# Tilty_Template.net
KiCad netlist of a schematic drawn in EAGLE
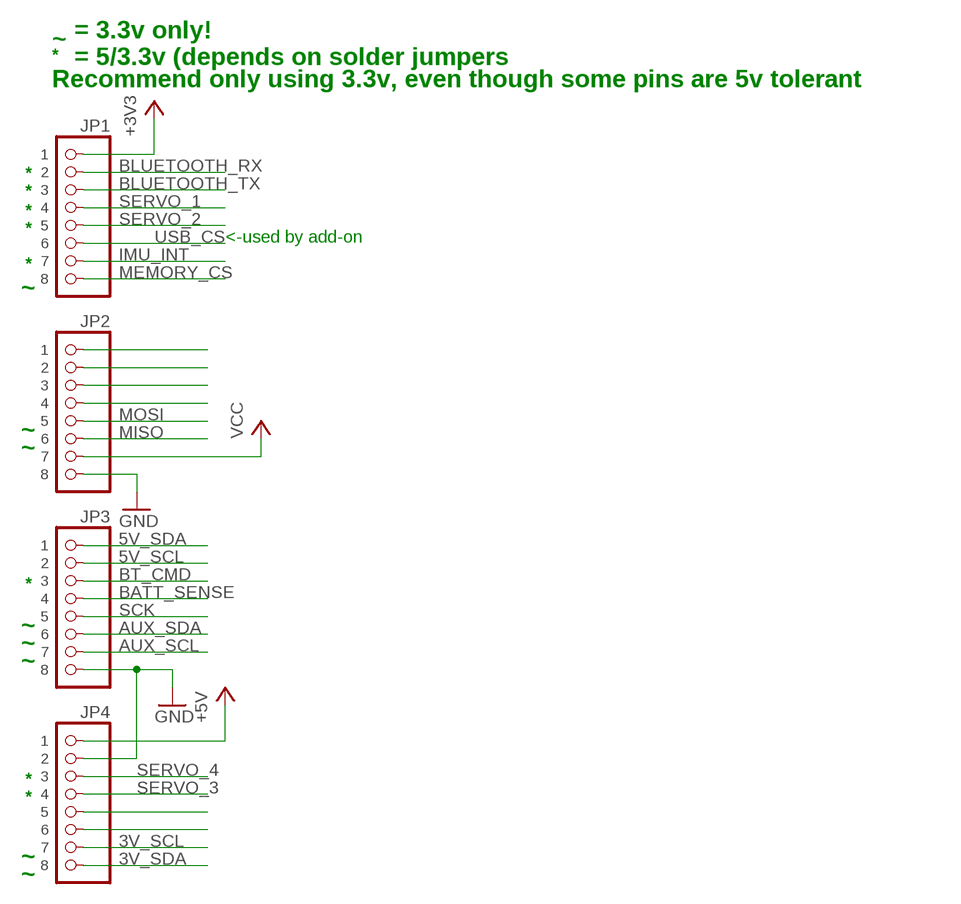
[diagram p0: schematic, sheet 1]

(export (version "E")
  (design (tool "Eeschema 10.0.6"))
  (components
    (comp (ref "JP1")
      (value "8-PIN_HEADER")
      (footprint "eagle-import:8-PIN_RECEPTACLE_LOCK_NO-SS")
      (libsource (lib "eagle-import") (part "8-PIN_HEADER"))
    )
    (comp (ref "JP2")
      (value "8-PIN_HEADER")
      (footprint "eagle-import:8-PIN_RECEPTACLE_LOCK_NO-SS")
      (libsource (lib "eagle-import") (part "8-PIN_HEADER"))
    )
    (comp (ref "JP3")
      (value "8-PIN_HEADER")
      (footprint "eagle-import:8-PIN_RECEPTACLE_LOCK_NO-SS")
      (libsource (lib "eagle-import") (part "8-PIN_HEADER"))
    )
    (comp (ref "JP4")
      (value "8-PIN_HEADER")
      (footprint "eagle-import:8-PIN_RECEPTACLE_LOCK_NO-SS")
      (libsource (lib "eagle-import") (part "8-PIN_HEADER"))
    )
  )
  (nets
    (net (code "1") (name "+3V3") (class "Default")
      (node (ref "JP1") (pin "P$1") (pinfunction "1_P$1") (pintype "passive"))
    )
    (net (code "2") (name "+5V") (class "Default")
      (node (ref "JP4") (pin "P$1") (pinfunction "1_P$1") (pintype "passive"))
    )
    (net (code "3") (name "/3V_SCL") (class "Default")
      (node (ref "JP4") (pin "P$7") (pinfunction "7_P$7") (pintype "passive"))
    )
    (net (code "4") (name "/3V_SDA") (class "Default")
      (node (ref "JP4") (pin "P$8") (pinfunction "8_P$8") (pintype "passive"))
    )
    (net (code "5") (name "/5V_SCL") (class "Default")
      (node (ref "JP3") (pin "P$2") (pinfunction "2_P$2") (pintype "passive"))
    )
    (net (code "6") (name "/5V_SDA") (class "Default")
      (node (ref "JP3") (pin "P$1") (pinfunction "1_P$1") (pintype "passive"))
    )
    (net (code "7") (name "/AUX_SCL") (class "Default")
      (node (ref "JP3") (pin "P$7") (pinfunction "7_P$7") (pintype "passive"))
    )
    (net (code "8") (name "/AUX_SDA") (class "Default")
      (node (ref "JP3") (pin "P$6") (pinfunction "6_P$6") (pintype "passive"))
    )
    (net (code "9") (name "/BATT_SENSE") (class "Default")
      (node (ref "JP3") (pin "P$4") (pinfunction "4_P$4") (pintype "passive"))
    )
    (net (code "10") (name "/BLUETOOTH_RX") (class "Default")
      (node (ref "JP1") (pin "P$2") (pinfunction "2_P$2") (pintype "passive"))
    )
    (net (code "11") (name "/BLUETOOTH_TX") (class "Default")
      (node (ref "JP1") (pin "P$3") (pinfunction "3_P$3") (pintype "passive"))
    )
    (net (code "12") (name "/BT_CMD") (class "Default")
      (node (ref "JP3") (pin "P$3") (pinfunction "3_P$3") (pintype "passive"))
    )
    (net (code "13") (name "/IMU_INT") (class "Default")
      (node (ref "JP1") (pin "P$7") (pinfunction "7_P$7") (pintype "passive"))
    )
    (net (code "14") (name "/MEMORY_CS") (class "Default")
      (node (ref "JP1") (pin "P$8") (pinfunction "8_P$8") (pintype "passive"))
    )
    (net (code "15") (name "/MISO") (class "Default")
      (node (ref "JP2") (pin "P$6") (pinfunction "6_P$6") (pintype "passive"))
    )
    (net (code "16") (name "/MOSI") (class "Default")
      (node (ref "JP2") (pin "P$5") (pinfunction "5_P$5") (pintype "passive"))
    )
    (net (code "17") (name "/SCK") (class "Default")
      (node (ref "JP3") (pin "P$5") (pinfunction "5_P$5") (pintype "passive"))
    )
    (net (code "18") (name "/SERVO_1") (class "Default")
      (node (ref "JP1") (pin "P$4") (pinfunction "4_P$4") (pintype "passive"))
    )
    (net (code "19") (name "/SERVO_2") (class "Default")
      (node (ref "JP1") (pin "P$5") (pinfunction "5_P$5") (pintype "passive"))
    )
    (net (code "20") (name "/SERVO_3") (class "Default")
      (node (ref "JP4") (pin "P$4") (pinfunction "4_P$4") (pintype "passive"))
    )
    (net (code "21") (name "/SERVO_4") (class "Default")
      (node (ref "JP4") (pin "P$3") (pinfunction "3_P$3") (pintype "passive"))
    )
    (net (code "22") (name "/USB_CS") (class "Default")
      (node (ref "JP1") (pin "P$6") (pinfunction "6_P$6") (pintype "passive"))
    )
    (net (code "23") (name "GND") (class "Default")
      (node (ref "JP2") (pin "P$8") (pinfunction "8_P$8") (pintype "passive"))
      (node (ref "JP3") (pin "P$8") (pinfunction "8_P$8") (pintype "passive"))
      (node (ref "JP4") (pin "P$2") (pinfunction "2_P$2") (pintype "passive"))
    )
    (net (code "24") (name "VCC") (class "Default")
      (node (ref "JP2") (pin "P$7") (pinfunction "7_P$7") (pintype "passive"))
    )
    (net (code "25") (name "unconnected-(JP2-1-PadP$1)") (class "Default")
      (node (ref "JP2") (pin "P$1") (pinfunction "1_P$1") (pintype "passive"))
    )
    (net (code "26") (name "unconnected-(JP2-2-PadP$2)") (class "Default")
      (node (ref "JP2") (pin "P$2") (pinfunction "2_P$2") (pintype "passive"))
    )
    (net (code "27") (name "unconnected-(JP2-3-PadP$3)") (class "Default")
      (node (ref "JP2") (pin "P$3") (pinfunction "3_P$3") (pintype "passive"))
    )
    (net (code "28") (name "unconnected-(JP2-4-PadP$4)") (class "Default")
      (node (ref "JP2") (pin "P$4") (pinfunction "4_P$4") (pintype "passive"))
    )
    (net (code "29") (name "unconnected-(JP4-5-PadP$5)") (class "Default")
      (node (ref "JP4") (pin "P$5") (pinfunction "5_P$5") (pintype "passive"))
    )
    (net (code "30") (name "unconnected-(JP4-6-PadP$6)") (class "Default")
      (node (ref "JP4") (pin "P$6") (pinfunction "6_P$6") (pintype "passive"))
    )
  )
)
